# Environment-V6-RS485-BasePcb.net
KiCad netlist of a schematic drawn in EAGLE
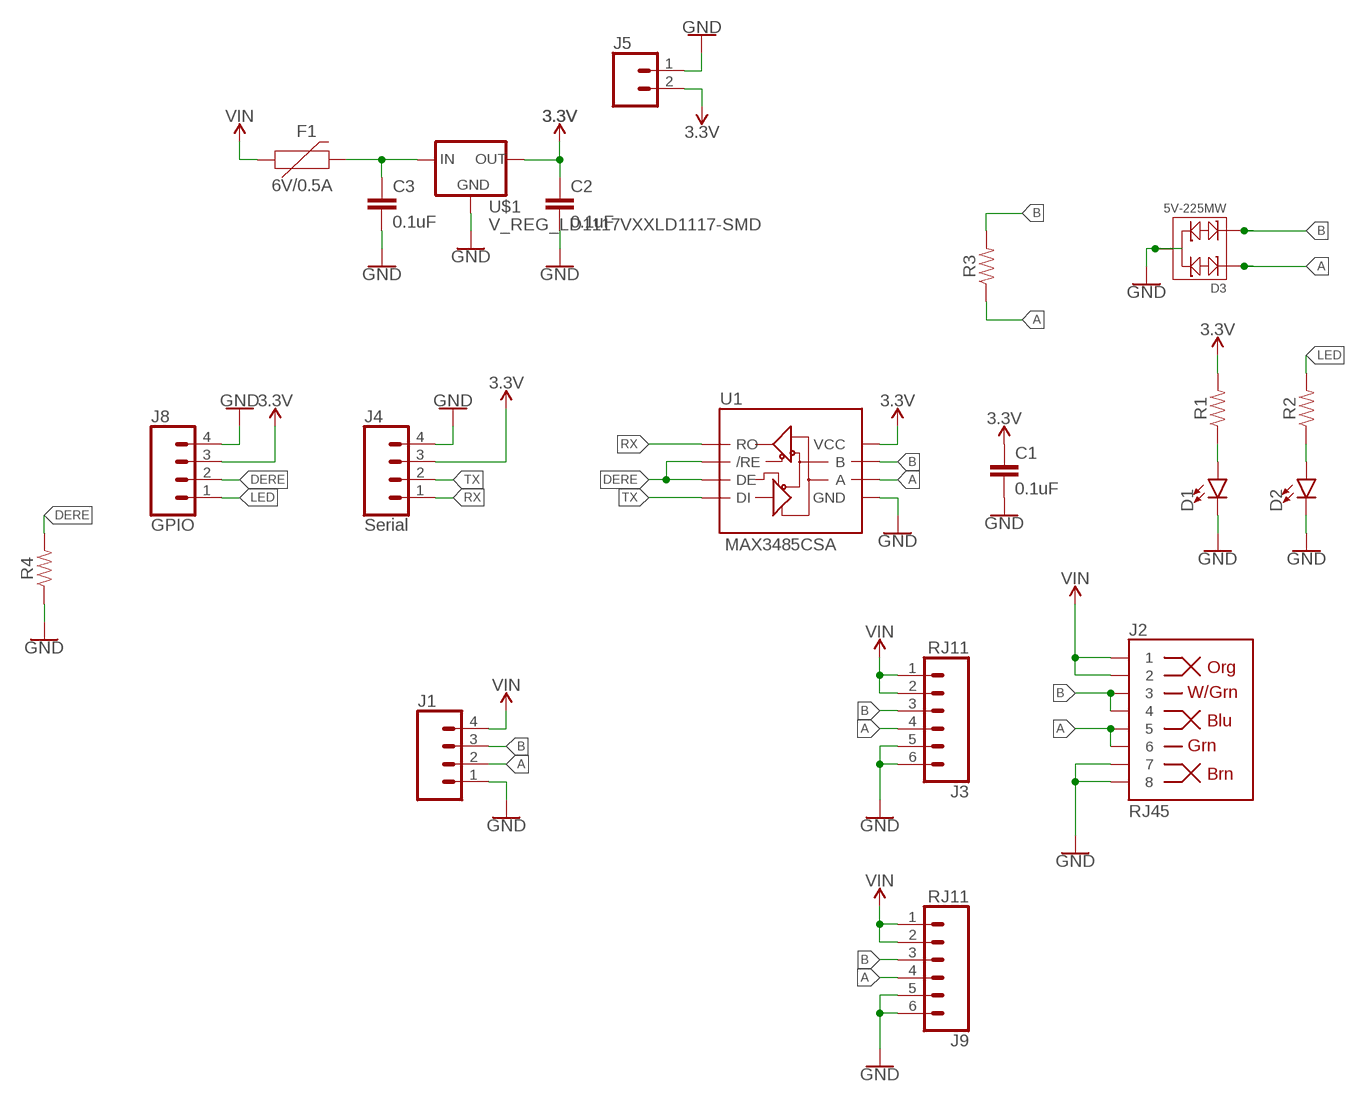
[diagram p0: schematic, sheet 1]

(export (version "E")
  (design (tool "Eeschema 10.0.6"))
  (components
    (comp (ref "C1")
      (value "0.1uF")
      (footprint "eagle-import:0805")
      (libsource (lib "eagle-import") (part "0.1UF-0805-25V"))
    )
    (comp (ref "C2")
      (value "0.1uF")
      (footprint "eagle-import:0805")
      (libsource (lib "eagle-import") (part "0.1UF-0805-25V"))
    )
    (comp (ref "C3")
      (value "0.1uF")
      (footprint "eagle-import:0805")
      (libsource (lib "eagle-import") (part "0.1UF-0805-25V"))
    )
    (comp (ref "D1")
      (value "LED1206")
      (footprint "eagle-import:LED-1206")
      (libsource (lib "eagle-import") (part "LED1206"))
    )
    (comp (ref "D2")
      (value "LED1206")
      (footprint "eagle-import:LED-1206")
      (libsource (lib "eagle-import") (part "LED1206"))
    )
    (comp (ref "D3")
      (value "5V-225MW")
      (footprint "eagle-import:SOT-23")
      (fields (field (name "MPN") "CESD5V0AP"))
      (libsource (lib "eagle-import") (part "SMD-DIODE-TVS-5V-225MW(SOT-23)"))
    )
    (comp (ref "F1")
      (value "6V/0.5A")
      (footprint "eagle-import:1206")
      (libsource (lib "eagle-import") (part "PPTC_HALF-AMP"))
    )
    (comp (ref "J1")
      (value "CONN_04SCREW")
      (footprint "eagle-import:SCREWTERMINAL-3.5MM-4")
      (libsource (lib "eagle-import") (part "CONN_04SCREW"))
    )
    (comp (ref "J2")
      (value "RJ45")
      (footprint "eagle-import:RJ45-8")
      (libsource (lib "eagle-import") (part "RJ45-8"))
    )
    (comp (ref "J3")
      (value "RJ11")
      (footprint "eagle-import:RJ11-6")
      (libsource (lib "eagle-import") (part "RJ11-6"))
    )
    (comp (ref "J4")
      (value "Serial")
      (footprint "eagle-import:JST-4-PH-GROVE")
      (libsource (lib "eagle-import") (part "CONN_04GROVE-JST-PH-4-2MM"))
    )
    (comp (ref "J5")
      (value "CONN_02-JST-2MM-SMT")
      (footprint "eagle-import:JST-2-SMD")
      (libsource (lib "eagle-import") (part "CONN_02-JST-2MM-SMT"))
    )
    (comp (ref "J8")
      (value "GPIO")
      (footprint "eagle-import:JST-4-PH-GROVE")
      (libsource (lib "eagle-import") (part "CONN_04GROVE-JST-PH-4-2MM"))
    )
    (comp (ref "J9")
      (value "RJ11")
      (footprint "eagle-import:RJ11-6")
      (libsource (lib "eagle-import") (part "RJ11-6"))
    )
    (comp (ref "R1")
      (value "RESISTOR0805")
      (footprint "eagle-import:0805")
      (libsource (lib "eagle-import") (part "RESISTOR0805"))
    )
    (comp (ref "R2")
      (value "RESISTOR0805")
      (footprint "eagle-import:0805")
      (libsource (lib "eagle-import") (part "RESISTOR0805"))
    )
    (comp (ref "R3")
      (value "RESISTOR0805")
      (footprint "eagle-import:0805")
      (libsource (lib "eagle-import") (part "RESISTOR0805"))
    )
    (comp (ref "R4")
      (value "RESISTOR0805")
      (footprint "eagle-import:0805")
      (libsource (lib "eagle-import") (part "RESISTOR0805"))
    )
    (comp (ref "U$1")
      (value "V_REG_LD1117VXXLD1117-SMD")
      (footprint "eagle-import:SOT223")
      (libsource (lib "eagle-import") (part "V_REG_LD1117VXXLD1117-SMD"))
    )
    (comp (ref "U1")
      (value "MAX3485CSA")
      (footprint "eagle-import:SO08")
      (libsource (lib "eagle-import") (part "RS485SOIC"))
    )
  )
  (nets
    (net (code "1") (name "3.3V") (class "Default")
      (node (ref "C1") (pin "1") (pinfunction "1_1") (pintype "passive"))
      (node (ref "C2") (pin "1") (pinfunction "1_1") (pintype "passive"))
      (node (ref "J4") (pin "3") (pinfunction "3_3") (pintype "passive"))
      (node (ref "J5") (pin "2") (pinfunction "1_2") (pintype "passive"))
      (node (ref "J8") (pin "3") (pinfunction "3_3") (pintype "passive"))
      (node (ref "R1") (pin "2") (pinfunction "2_2") (pintype "passive"))
      (node (ref "U$1") (pin "2") (pinfunction "OUT_2") (pintype "passive"))
      (node (ref "U1") (pin "8") (pinfunction "VCC_8") (pintype "bidirectional"))
    )
    (net (code "2") (name "A") (class "Default")
      (node (ref "D3") (pin "1") (pinfunction "1_1") (pintype "power_in"))
      (node (ref "J1") (pin "2") (pinfunction "2_2") (pintype "passive"))
      (node (ref "J2") (pin "5") (pinfunction "5_5") (pintype "bidirectional"))
      (node (ref "J2") (pin "6") (pinfunction "6_6") (pintype "bidirectional"))
      (node (ref "J3") (pin "4") (pinfunction "4_4") (pintype "passive"))
      (node (ref "J9") (pin "4") (pinfunction "4_4") (pintype "passive"))
      (node (ref "R3") (pin "1") (pinfunction "1_1") (pintype "passive"))
      (node (ref "U1") (pin "6") (pinfunction "A_6") (pintype "bidirectional"))
    )
    (net (code "3") (name "B") (class "Default")
      (node (ref "D3") (pin "2") (pinfunction "2_2") (pintype "power_in"))
      (node (ref "J1") (pin "3") (pinfunction "3_3") (pintype "passive"))
      (node (ref "J2") (pin "3") (pinfunction "3_3") (pintype "bidirectional"))
      (node (ref "J2") (pin "4") (pinfunction "4_4") (pintype "bidirectional"))
      (node (ref "J3") (pin "3") (pinfunction "3_3") (pintype "passive"))
      (node (ref "J9") (pin "3") (pinfunction "3_3") (pintype "passive"))
      (node (ref "R3") (pin "2") (pinfunction "2_2") (pintype "passive"))
      (node (ref "U1") (pin "7") (pinfunction "B_7") (pintype "bidirectional"))
    )
    (net (code "4") (name "DERE") (class "Default")
      (node (ref "J8") (pin "2") (pinfunction "2_2") (pintype "passive"))
      (node (ref "R4") (pin "2") (pinfunction "2_2") (pintype "passive"))
      (node (ref "U1") (pin "2") (pinfunction "/RE_2") (pintype "bidirectional"))
      (node (ref "U1") (pin "3") (pinfunction "DE_3") (pintype "bidirectional"))
    )
    (net (code "5") (name "GND") (class "Default")
      (node (ref "C1") (pin "2") (pinfunction "2_2") (pintype "passive"))
      (node (ref "C2") (pin "2") (pinfunction "2_2") (pintype "passive"))
      (node (ref "C3") (pin "2") (pinfunction "2_2") (pintype "passive"))
      (node (ref "D1") (pin "C") (pinfunction "C_C") (pintype "passive"))
      (node (ref "D2") (pin "C") (pinfunction "C_C") (pintype "passive"))
      (node (ref "D3") (pin "3") (pinfunction "3_3") (pintype "bidirectional"))
      (node (ref "J1") (pin "1") (pinfunction "1_1") (pintype "passive"))
      (node (ref "J2") (pin "7") (pinfunction "7_7") (pintype "bidirectional"))
      (node (ref "J2") (pin "8") (pinfunction "8_8") (pintype "bidirectional"))
      (node (ref "J3") (pin "5") (pinfunction "5_5") (pintype "passive"))
      (node (ref "J3") (pin "6") (pinfunction "6_6") (pintype "passive"))
      (node (ref "J4") (pin "4") (pinfunction "4_4") (pintype "passive"))
      (node (ref "J5") (pin "1") (pinfunction "2_1") (pintype "passive"))
      (node (ref "J8") (pin "4") (pinfunction "4_4") (pintype "passive"))
      (node (ref "J9") (pin "5") (pinfunction "5_5") (pintype "passive"))
      (node (ref "J9") (pin "6") (pinfunction "6_6") (pintype "passive"))
      (node (ref "R4") (pin "1") (pinfunction "1_1") (pintype "passive"))
      (node (ref "U$1") (pin "1") (pinfunction "GND_1") (pintype "input"))
      (node (ref "U1") (pin "5") (pinfunction "GND_5") (pintype "bidirectional"))
    )
    (net (code "6") (name "LED") (class "Default")
      (node (ref "J8") (pin "1") (pinfunction "1_1") (pintype "passive"))
      (node (ref "R2") (pin "2") (pinfunction "2_2") (pintype "passive"))
    )
    (net (code "7") (name "Net-(D1-PadA)") (class "Default")
      (node (ref "D1") (pin "A") (pinfunction "A_A") (pintype "passive"))
      (node (ref "R1") (pin "1") (pinfunction "1_1") (pintype "passive"))
    )
    (net (code "8") (name "Net-(D2-PadA)") (class "Default")
      (node (ref "D2") (pin "A") (pinfunction "A_A") (pintype "passive"))
      (node (ref "R2") (pin "1") (pinfunction "1_1") (pintype "passive"))
    )
    (net (code "9") (name "Net-(U$1-IN)") (class "Default")
      (node (ref "C3") (pin "1") (pinfunction "1_1") (pintype "passive"))
      (node (ref "F1") (pin "2") (pinfunction "2_2") (pintype "bidirectional"))
      (node (ref "U$1") (pin "3") (pinfunction "IN_3") (pintype "input"))
    )
    (net (code "10") (name "RX") (class "Default")
      (node (ref "J4") (pin "1") (pinfunction "1_1") (pintype "passive"))
      (node (ref "U1") (pin "1") (pinfunction "RO_1") (pintype "bidirectional"))
    )
    (net (code "11") (name "TX") (class "Default")
      (node (ref "J4") (pin "2") (pinfunction "2_2") (pintype "passive"))
      (node (ref "U1") (pin "4") (pinfunction "DI_4") (pintype "bidirectional"))
    )
    (net (code "12") (name "VIN") (class "Default")
      (node (ref "F1") (pin "1") (pinfunction "1_1") (pintype "bidirectional"))
      (node (ref "J1") (pin "4") (pinfunction "4_4") (pintype "passive"))
      (node (ref "J2") (pin "1") (pinfunction "1_1") (pintype "bidirectional"))
      (node (ref "J2") (pin "2") (pinfunction "2_2") (pintype "bidirectional"))
      (node (ref "J3") (pin "1") (pinfunction "1_1") (pintype "passive"))
      (node (ref "J3") (pin "2") (pinfunction "2_2") (pintype "passive"))
      (node (ref "J9") (pin "1") (pinfunction "1_1") (pintype "passive"))
      (node (ref "J9") (pin "2") (pinfunction "2_2") (pintype "passive"))
    )
  )
)
